# Temperature_Sensors.net
KiCad netlist of a schematic drawn in Altium Designer
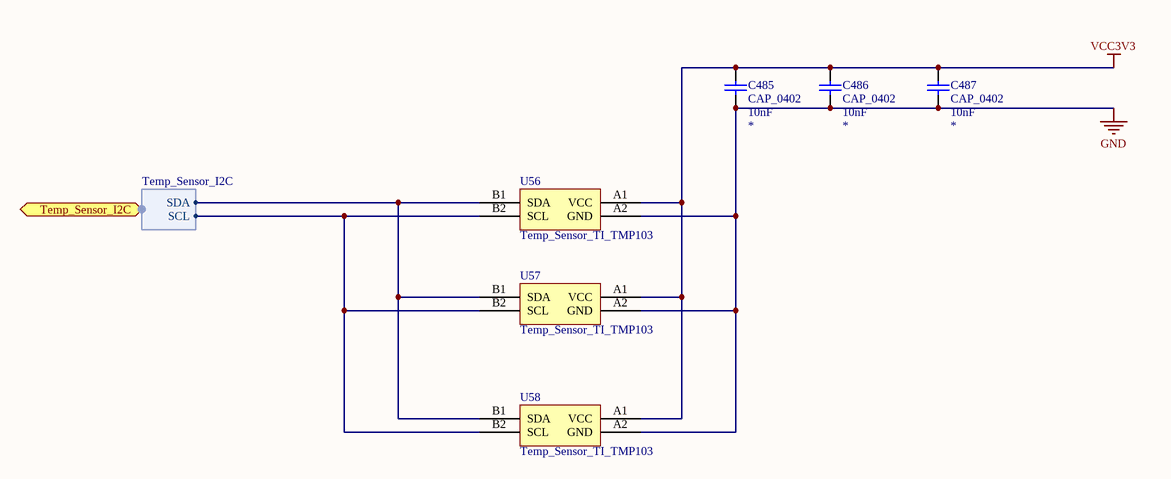
[diagram p0: Temperature_Sensors.SchDoc]

(export (version "E")
  (design (tool "Eeschema 10.0.6"))
  (components
    (comp (ref "C485")
      (value "CAP_0402")
      (footprint "CAPC0402(1005)60_N")
      (description "10000pF, ceramic, 10% 6.3V X5R, 0402")
      (fields
        (field (name "ALTIUM_VALUE") "10nF")
        (field (name "TOLERANCE") "*")
        (field (name "PART NUMBER") "GRM155R60J103KA01D")
        (field (name "MANUFACTURER") "Murata Electronics North America")
      )
      (libsource (lib "COMRAD_Database") (part "CAP_0402"))
    )
    (comp (ref "C486")
      (value "CAP_0402")
      (footprint "CAPC0402(1005)60_N")
      (description "10000pF, ceramic, 10% 6.3V X5R, 0402")
      (fields
        (field (name "ALTIUM_VALUE") "10nF")
        (field (name "TOLERANCE") "*")
        (field (name "PART NUMBER") "GRM155R60J103KA01D")
        (field (name "MANUFACTURER") "Murata Electronics North America")
      )
      (libsource (lib "COMRAD_Database") (part "CAP_0402"))
    )
    (comp (ref "C487")
      (value "CAP_0402")
      (footprint "CAPC0402(1005)60_N")
      (description "10000pF, ceramic, 10% 6.3V X5R, 0402")
      (fields
        (field (name "ALTIUM_VALUE") "10nF")
        (field (name "TOLERANCE") "*")
        (field (name "PART NUMBER") "GRM155R60J103KA01D")
        (field (name "MANUFACTURER") "Murata Electronics North America")
      )
      (libsource (lib "COMRAD_Database") (part "CAP_0402"))
    )
    (comp (ref "U56")
      (value "Temp_Sensor_TI_TMP103")
      (footprint "Temp_Sensor_TI_TMP103_XBGA-4")
      (description "IC TEMP SENSOR DGTL SMBUS 4DSBGA, Address - A")
      (fields (field (name "PART NUMBER") "TMP103AYFFR") (field (name "MANUFACTURER") "Texas Instruments"))
      (libsource (lib "COMRAD_Database") (part "Temp_Sensor_TI_TMP103"))
    )
    (comp (ref "U57")
      (value "Temp_Sensor_TI_TMP103")
      (footprint "Temp_Sensor_TI_TMP103_XBGA-4")
      (description "IC TEMP SENSOR DGTL SMBUS 4DSBGA, Address - B")
      (fields (field (name "PART NUMBER") "TMP103BYFFR") (field (name "MANUFACTURER") "Texas Instruments"))
      (libsource (lib "COMRAD_Database") (part "Temp_Sensor_TI_TMP103"))
    )
    (comp (ref "U58")
      (value "Temp_Sensor_TI_TMP103")
      (footprint "Temp_Sensor_TI_TMP103_XBGA-4")
      (description "IC TEMP SENSOR DGTL SMBUS 4DSBGA, Address - C")
      (fields (field (name "PART NUMBER") "TMP103CYFFR") (field (name "MANUFACTURER") "Texas Instruments"))
      (libsource (lib "COMRAD_Database") (part "Temp_Sensor_TI_TMP103"))
    )
  )
  (nets
    (net (code "3") (name "GND") (class "Default")
      (node (ref "C485") (pin "1") (pinfunction "1_1") (pintype "passive"))
      (node (ref "C486") (pin "1") (pinfunction "1_1") (pintype "passive"))
      (node (ref "C487") (pin "1") (pinfunction "1_1") (pintype "passive"))
      (node (ref "U56") (pin "A2") (pinfunction "GND_A2") (pintype "passive"))
      (node (ref "U57") (pin "A2") (pinfunction "GND_A2") (pintype "passive"))
      (node (ref "U58") (pin "A2") (pinfunction "GND_A2") (pintype "passive"))
    )
    (net (code "4") (name "Net-(U56-SCL)") (class "Default")
      (node (ref "U56") (pin "B2") (pinfunction "SCL_B2") (pintype "passive"))
      (node (ref "U57") (pin "B2") (pinfunction "SCL_B2") (pintype "passive"))
      (node (ref "U58") (pin "B2") (pinfunction "SCL_B2") (pintype "passive"))
    )
    (net (code "5") (name "Net-(U56-SDA)") (class "Default")
      (node (ref "U56") (pin "B1") (pinfunction "SDA_B1") (pintype "passive"))
      (node (ref "U57") (pin "B1") (pinfunction "SDA_B1") (pintype "passive"))
      (node (ref "U58") (pin "B1") (pinfunction "SDA_B1") (pintype "passive"))
    )
    (net (code "6") (name "VCC3V3") (class "Default")
      (node (ref "C485") (pin "2") (pinfunction "2_2") (pintype "passive"))
      (node (ref "C486") (pin "2") (pinfunction "2_2") (pintype "passive"))
      (node (ref "C487") (pin "2") (pinfunction "2_2") (pintype "passive"))
      (node (ref "U56") (pin "A1") (pinfunction "VCC_A1") (pintype "passive"))
      (node (ref "U57") (pin "A1") (pinfunction "VCC_A1") (pintype "passive"))
      (node (ref "U58") (pin "A1") (pinfunction "VCC_A1") (pintype "passive"))
    )
  )
)
